# M452sx.net
KiCad netlist of a schematic drawn in EAGLE
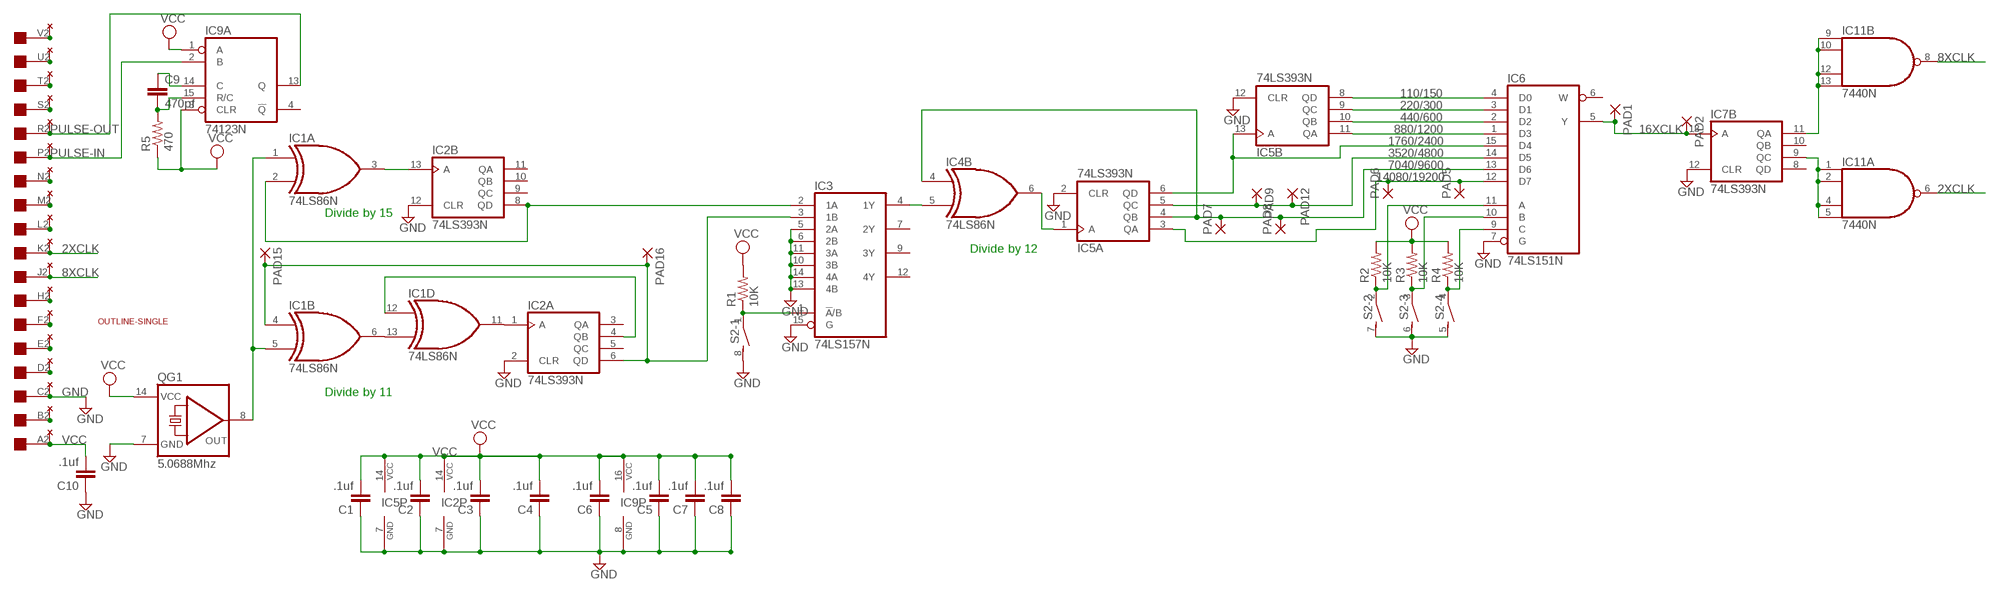
[diagram p0: schematic, sheet 1]

(export (version "E")
  (design (tool "Eeschema 10.0.6"))
  (components
    (comp (ref "C1")
      (value ".1uf")
      (footprint "eagle-import:C050-025X075")
      (libsource (lib "eagle-import") (part "C-EU050-025X075"))
    )
    (comp (ref "C2")
      (value ".1uf")
      (footprint "eagle-import:C050-025X075")
      (libsource (lib "eagle-import") (part "C-EU050-025X075"))
    )
    (comp (ref "C3")
      (value ".1uf")
      (footprint "eagle-import:C050-025X075")
      (libsource (lib "eagle-import") (part "C-EU050-025X075"))
    )
    (comp (ref "C4")
      (value ".1uf")
      (footprint "eagle-import:C050-025X075")
      (libsource (lib "eagle-import") (part "C-EU050-025X075"))
    )
    (comp (ref "C5")
      (value ".1uf")
      (footprint "eagle-import:C050-025X075")
      (libsource (lib "eagle-import") (part "C-EU050-025X075"))
    )
    (comp (ref "C6")
      (value ".1uf")
      (footprint "eagle-import:C050-025X075")
      (libsource (lib "eagle-import") (part "C-EU050-025X075"))
    )
    (comp (ref "C7")
      (value ".1uf")
      (footprint "eagle-import:C050-025X075")
      (libsource (lib "eagle-import") (part "C-EU050-025X075"))
    )
    (comp (ref "C8")
      (value ".1uf")
      (footprint "eagle-import:C050-025X075")
      (libsource (lib "eagle-import") (part "C-EU050-025X075"))
    )
    (comp (ref "C9")
      (value "470pf")
      (footprint "eagle-import:C050-025X075")
      (libsource (lib "eagle-import") (part "C-EU050-025X075"))
    )
    (comp (ref "C10")
      (value ".1uf")
      (footprint "eagle-import:C050-025X075")
      (libsource (lib "eagle-import") (part "C-EU050-025X075"))
    )
    (comp (ref "IC1")
      (value "74LS86N")
      (footprint "eagle-import:DIL14")
      (libsource (lib "eagle-import") (part "7486NLS"))
    )
    (comp (ref "IC2")
      (value "74LS393N")
      (footprint "eagle-import:DIL14")
      (libsource (lib "eagle-import") (part "74393NLS"))
    )
    (comp (ref "IC3")
      (value "74LS157N")
      (footprint "eagle-import:DIL16")
      (libsource (lib "eagle-import") (part "74157NLS"))
    )
    (comp (ref "IC4")
      (value "74LS86N")
      (footprint "eagle-import:DIL14")
      (libsource (lib "eagle-import") (part "7486NLS"))
    )
    (comp (ref "IC5")
      (value "74LS393N")
      (footprint "eagle-import:DIL14")
      (libsource (lib "eagle-import") (part "74393NLS"))
    )
    (comp (ref "IC6")
      (value "74LS151N")
      (footprint "eagle-import:DIL16")
      (libsource (lib "eagle-import") (part "74151N"))
    )
    (comp (ref "IC7")
      (value "74LS393N")
      (footprint "eagle-import:DIL14")
      (libsource (lib "eagle-import") (part "74393NLS"))
    )
    (comp (ref "IC9")
      (value "74123N")
      (footprint "eagle-import:DIL16")
      (libsource (lib "eagle-import") (part "74123N"))
    )
    (comp (ref "IC11")
      (value "7440N")
      (footprint "eagle-import:DIL14")
      (libsource (lib "eagle-import") (part "7420NS"))
    )
    (comp (ref "PAD1")
      (value "1,6/0,8")
      (footprint "eagle-import:1,6_0,8")
      (libsource (lib "eagle-import") (part "1,6/0,8"))
    )
    (comp (ref "PAD2")
      (value "1,6/0,8")
      (footprint "eagle-import:1,6_0,8")
      (libsource (lib "eagle-import") (part "1,6/0,8"))
    )
    (comp (ref "PAD5")
      (value "1,6/0,8")
      (footprint "eagle-import:1,6_0,8")
      (libsource (lib "eagle-import") (part "1,6/0,8"))
    )
    (comp (ref "PAD6")
      (value "1,6/0,8")
      (footprint "eagle-import:1,6_0,8")
      (libsource (lib "eagle-import") (part "1,6/0,8"))
    )
    (comp (ref "PAD7")
      (value "1,6/0,8")
      (footprint "eagle-import:1,6_0,8")
      (libsource (lib "eagle-import") (part "1,6/0,8"))
    )
    (comp (ref "PAD8")
      (value "1,6/0,8")
      (footprint "eagle-import:1,6_0,8")
      (libsource (lib "eagle-import") (part "1,6/0,8"))
    )
    (comp (ref "PAD9")
      (value "1,6/0,8")
      (footprint "eagle-import:1,6_0,8")
      (libsource (lib "eagle-import") (part "1,6/0,8"))
    )
    (comp (ref "PAD12")
      (value "1,6/0,8")
      (footprint "eagle-import:1,6_0,8")
      (libsource (lib "eagle-import") (part "1,6/0,8"))
    )
    (comp (ref "PAD15")
      (value "1,6/0,8")
      (footprint "eagle-import:1,6_0,8")
      (libsource (lib "eagle-import") (part "1,6/0,8"))
    )
    (comp (ref "PAD16")
      (value "1,6/0,8")
      (footprint "eagle-import:1,6_0,8")
      (libsource (lib "eagle-import") (part "1,6/0,8"))
    )
    (comp (ref "QG1")
      (value "5.0688Mhz")
      (footprint "eagle-import:DIL14S")
      (libsource (lib "eagle-import") (part "QG5860"))
    )
    (comp (ref "R1")
      (value "10K")
      (footprint "eagle-import:0204_7")
      (libsource (lib "eagle-import") (part "R-US_0204/7"))
    )
    (comp (ref "R2")
      (value "10K")
      (footprint "eagle-import:0204_7")
      (libsource (lib "eagle-import") (part "R-US_0204/7"))
    )
    (comp (ref "R3")
      (value "10K")
      (footprint "eagle-import:0204_7")
      (libsource (lib "eagle-import") (part "R-US_0204/7"))
    )
    (comp (ref "R4")
      (value "10K")
      (footprint "eagle-import:0204_7")
      (libsource (lib "eagle-import") (part "R-US_0204/7"))
    )
    (comp (ref "R5")
      (value "470")
      (footprint "eagle-import:0204_7")
      (libsource (lib "eagle-import") (part "R-US_0204/7"))
    )
    (comp (ref "S2")
      (value "DIP04S")
      (footprint "eagle-import:DIP04S")
      (libsource (lib "eagle-import") (part "DIP04S"))
    )
    (comp (ref "U$2")
      (value "EDGE-1")
      (footprint "eagle-import:EDGE-CON1")
      (libsource (lib "eagle-import") (part "EDGE-1"))
    )
    (comp (ref "U$3")
      (value "THRU-HOLE1")
      (footprint "eagle-import:THRU-HOLE1")
      (libsource (lib "eagle-import") (part "THRU-HOLE1"))
    )
    (comp (ref "U$4")
      (value "OUTLINE-SINGLE")
      (footprint "eagle-import:SINGLE")
      (libsource (lib "eagle-import") (part "OUTLINE-SINGLE"))
    )
  )
  (nets
    (net (code "1") (name "/2XCLK") (class "Default")
      (node (ref "IC11") (pin "6") (pinfunction "O_6") (pintype "output"))
      (node (ref "U$2") (pin "K2") (pinfunction "1_K2") (pintype "bidirectional"))
      (node (ref "U$3") (pin "K2") (pinfunction "P$1_K2") (pintype "passive"))
    )
    (net (code "2") (name "/8XCLK") (class "Default")
      (node (ref "IC11") (pin "8") (pinfunction "O_8") (pintype "output"))
      (node (ref "U$2") (pin "J2") (pinfunction "1_J2") (pintype "bidirectional"))
      (node (ref "U$3") (pin "J2") (pinfunction "P$1_J2") (pintype "passive"))
    )
    (net (code "3") (name "/16XCLK") (class "Default")
      (node (ref "IC6") (pin "5") (pinfunction "Y_5") (pintype "output"))
      (node (ref "IC7") (pin "13") (pinfunction "A_13") (pintype "input"))
      (node (ref "PAD1") (pin "1") (pinfunction "P_1") (pintype "passive"))
      (node (ref "PAD2") (pin "1") (pinfunction "P_1") (pintype "passive"))
    )
    (net (code "4") (name "/110{slash}150") (class "Default")
      (node (ref "IC5") (pin "8") (pinfunction "QD_8") (pintype "output"))
      (node (ref "IC6") (pin "4") (pinfunction "D0_4") (pintype "input"))
    )
    (net (code "5") (name "/220{slash}300") (class "Default")
      (node (ref "IC5") (pin "9") (pinfunction "QC_9") (pintype "output"))
      (node (ref "IC6") (pin "3") (pinfunction "D1_3") (pintype "input"))
    )
    (net (code "6") (name "/440{slash}600") (class "Default")
      (node (ref "IC5") (pin "10") (pinfunction "QB_10") (pintype "output"))
      (node (ref "IC6") (pin "2") (pinfunction "D2_2") (pintype "input"))
    )
    (net (code "7") (name "/880{slash}1200") (class "Default")
      (node (ref "IC5") (pin "11") (pinfunction "QA_11") (pintype "output"))
      (node (ref "IC6") (pin "1") (pinfunction "D3_1") (pintype "input"))
    )
    (net (code "8") (name "/1760{slash}2400") (class "Default")
      (node (ref "IC5") (pin "13") (pinfunction "A_13") (pintype "input"))
      (node (ref "IC5") (pin "6") (pinfunction "QD_6") (pintype "output"))
      (node (ref "IC6") (pin "15") (pinfunction "D4_15") (pintype "input"))
    )
    (net (code "9") (name "/3520{slash}4800") (class "Default")
      (node (ref "IC5") (pin "5") (pinfunction "QC_5") (pintype "output"))
      (node (ref "IC6") (pin "14") (pinfunction "D5_14") (pintype "input"))
      (node (ref "PAD12") (pin "1") (pinfunction "P_1") (pintype "passive"))
      (node (ref "PAD9") (pin "1") (pinfunction "P_1") (pintype "passive"))
    )
    (net (code "10") (name "/7040{slash}9600") (class "Default")
      (node (ref "IC4") (pin "4") (pinfunction "I0_4") (pintype "input"))
      (node (ref "IC5") (pin "4") (pinfunction "QB_4") (pintype "output"))
      (node (ref "IC6") (pin "13") (pinfunction "D6_13") (pintype "input"))
      (node (ref "PAD7") (pin "1") (pinfunction "P_1") (pintype "passive"))
      (node (ref "PAD8") (pin "1") (pinfunction "P_1") (pintype "passive"))
    )
    (net (code "11") (name "/14080{slash}19200") (class "Default")
      (node (ref "IC5") (pin "3") (pinfunction "QA_3") (pintype "output"))
      (node (ref "IC6") (pin "12") (pinfunction "D7_12") (pintype "input"))
      (node (ref "PAD5") (pin "1") (pinfunction "P_1") (pintype "passive"))
      (node (ref "PAD6") (pin "1") (pinfunction "P_1") (pintype "passive"))
    )
    (net (code "12") (name "/PULSE-IN") (class "Default")
      (node (ref "IC9") (pin "2") (pinfunction "B_2") (pintype "input"))
      (node (ref "U$2") (pin "P2") (pinfunction "1_P2") (pintype "bidirectional"))
      (node (ref "U$3") (pin "P2") (pinfunction "P$1_P2") (pintype "passive"))
    )
    (net (code "13") (name "/PULSE-OUT") (class "Default")
      (node (ref "IC9") (pin "13") (pinfunction "Q_13") (pintype "output"))
      (node (ref "U$2") (pin "R2") (pinfunction "1_R2") (pintype "bidirectional"))
      (node (ref "U$3") (pin "R2") (pinfunction "P$1_R2") (pintype "passive"))
    )
    (net (code "14") (name "GND") (class "Default")
      (node (ref "C1") (pin "1") (pinfunction "1_1") (pintype "passive"))
      (node (ref "C10") (pin "1") (pinfunction "1_1") (pintype "passive"))
      (node (ref "C2") (pin "1") (pinfunction "1_1") (pintype "passive"))
      (node (ref "C3") (pin "1") (pinfunction "1_1") (pintype "passive"))
      (node (ref "C4") (pin "1") (pinfunction "1_1") (pintype "passive"))
      (node (ref "C5") (pin "1") (pinfunction "1_1") (pintype "passive"))
      (node (ref "C6") (pin "1") (pinfunction "1_1") (pintype "passive"))
      (node (ref "C7") (pin "1") (pinfunction "1_1") (pintype "passive"))
      (node (ref "C8") (pin "1") (pinfunction "1_1") (pintype "passive"))
      (node (ref "IC2") (pin "12") (pinfunction "CLR_12") (pintype "input"))
      (node (ref "IC2") (pin "2") (pinfunction "CLR_2") (pintype "input"))
      (node (ref "IC2") (pin "7") (pinfunction "GND_7") (pintype "power_in"))
      (node (ref "IC3") (pin "10") (pinfunction "3B_10") (pintype "input"))
      (node (ref "IC3") (pin "11") (pinfunction "3A_11") (pintype "input"))
      (node (ref "IC3") (pin "13") (pinfunction "4B_13") (pintype "input"))
      (node (ref "IC3") (pin "14") (pinfunction "4A_14") (pintype "input"))
      (node (ref "IC3") (pin "15") (pinfunction "G_15") (pintype "input"))
      (node (ref "IC3") (pin "5") (pinfunction "2A_5") (pintype "input"))
      (node (ref "IC3") (pin "6") (pinfunction "2B_6") (pintype "input"))
      (node (ref "IC5") (pin "12") (pinfunction "CLR_12") (pintype "input"))
      (node (ref "IC5") (pin "2") (pinfunction "CLR_2") (pintype "input"))
      (node (ref "IC5") (pin "7") (pinfunction "GND_7") (pintype "power_in"))
      (node (ref "IC6") (pin "7") (pinfunction "G_7") (pintype "input"))
      (node (ref "IC7") (pin "12") (pinfunction "CLR_12") (pintype "input"))
      (node (ref "IC9") (pin "8") (pinfunction "GND_8") (pintype "power_in"))
      (node (ref "QG1") (pin "7") (pinfunction "GND_7") (pintype "power_in"))
      (node (ref "S2") (pin "5") (pinfunction "2_5") (pintype "passive"))
      (node (ref "S2") (pin "6") (pinfunction "2_6") (pintype "passive"))
      (node (ref "S2") (pin "7") (pinfunction "2_7") (pintype "passive"))
      (node (ref "S2") (pin "8") (pinfunction "2_8") (pintype "passive"))
      (node (ref "U$2") (pin "C2") (pinfunction "1_C2") (pintype "bidirectional"))
      (node (ref "U$3") (pin "C2") (pinfunction "P$1_C2") (pintype "passive"))
    )
    (net (code "15") (name "Net-(IC1A-I0)") (class "Default")
      (node (ref "IC1") (pin "1") (pinfunction "I0_1") (pintype "input"))
      (node (ref "IC1") (pin "5") (pinfunction "I1_5") (pintype "input"))
      (node (ref "QG1") (pin "8") (pinfunction "OUT_8") (pintype "output"))
    )
    (net (code "16") (name "Net-(IC1A-I1)") (class "Default")
      (node (ref "IC1") (pin "2") (pinfunction "I1_2") (pintype "input"))
      (node (ref "IC2") (pin "8") (pinfunction "QD_8") (pintype "output"))
      (node (ref "IC3") (pin "2") (pinfunction "1A_2") (pintype "input"))
    )
    (net (code "17") (name "Net-(IC1A-O)") (class "Default")
      (node (ref "IC1") (pin "3") (pinfunction "O_3") (pintype "output"))
      (node (ref "IC2") (pin "13") (pinfunction "A_13") (pintype "input"))
    )
    (net (code "18") (name "Net-(IC1B-I0)") (class "Default")
      (node (ref "IC1") (pin "4") (pinfunction "I0_4") (pintype "input"))
      (node (ref "IC2") (pin "6") (pinfunction "QD_6") (pintype "output"))
      (node (ref "IC3") (pin "3") (pinfunction "1B_3") (pintype "input"))
      (node (ref "PAD15") (pin "1") (pinfunction "P_1") (pintype "passive"))
      (node (ref "PAD16") (pin "1") (pinfunction "P_1") (pintype "passive"))
    )
    (net (code "19") (name "Net-(IC1B-O)") (class "Default")
      (node (ref "IC1") (pin "13") (pinfunction "I1_13") (pintype "input"))
      (node (ref "IC1") (pin "6") (pinfunction "O_6") (pintype "output"))
    )
    (net (code "20") (name "Net-(IC1D-I0)") (class "Default")
      (node (ref "IC1") (pin "12") (pinfunction "I0_12") (pintype "input"))
      (node (ref "IC2") (pin "4") (pinfunction "QB_4") (pintype "output"))
    )
    (net (code "21") (name "Net-(IC1D-O)") (class "Default")
      (node (ref "IC1") (pin "11") (pinfunction "O_11") (pintype "output"))
      (node (ref "IC2") (pin "1") (pinfunction "A_1") (pintype "input"))
    )
    (net (code "22") (name "Net-(IC3A-1Y)") (class "Default")
      (node (ref "IC3") (pin "4") (pinfunction "1Y_4") (pintype "output"))
      (node (ref "IC4") (pin "5") (pinfunction "I1_5") (pintype "input"))
    )
    (net (code "23") (name "Net-(IC3A-~{A}{slash}B)") (class "Default")
      (node (ref "IC3") (pin "1") (pinfunction "~{A}/B_1") (pintype "input"))
      (node (ref "R1") (pin "1") (pinfunction "1_1") (pintype "passive"))
      (node (ref "S2") (pin "1") (pinfunction "1_1") (pintype "passive"))
    )
    (net (code "24") (name "Net-(IC4B-O)") (class "Default")
      (node (ref "IC4") (pin "6") (pinfunction "O_6") (pintype "output"))
      (node (ref "IC5") (pin "1") (pinfunction "A_1") (pintype "input"))
    )
    (net (code "25") (name "Net-(IC6A-A)") (class "Default")
      (node (ref "IC6") (pin "11") (pinfunction "A_11") (pintype "input"))
      (node (ref "R2") (pin "1") (pinfunction "1_1") (pintype "passive"))
      (node (ref "S2") (pin "2") (pinfunction "1_2") (pintype "passive"))
    )
    (net (code "26") (name "Net-(IC6A-B)") (class "Default")
      (node (ref "IC6") (pin "10") (pinfunction "B_10") (pintype "input"))
      (node (ref "R3") (pin "1") (pinfunction "1_1") (pintype "passive"))
      (node (ref "S2") (pin "3") (pinfunction "1_3") (pintype "passive"))
    )
    (net (code "27") (name "Net-(IC6A-C)") (class "Default")
      (node (ref "IC6") (pin "9") (pinfunction "C_9") (pintype "input"))
      (node (ref "R4") (pin "1") (pinfunction "1_1") (pintype "passive"))
      (node (ref "S2") (pin "4") (pinfunction "1_4") (pintype "passive"))
    )
    (net (code "28") (name "Net-(IC9A-C)") (class "Default")
      (node (ref "C9") (pin "1") (pinfunction "1_1") (pintype "passive"))
      (node (ref "IC9") (pin "14") (pinfunction "C_14") (pintype "input"))
    )
    (net (code "29") (name "Net-(IC9A-R{slash}C)") (class "Default")
      (node (ref "C9") (pin "2") (pinfunction "2_2") (pintype "passive"))
      (node (ref "IC9") (pin "15") (pinfunction "R/C_15") (pintype "input"))
      (node (ref "R5") (pin "2") (pinfunction "2_2") (pintype "passive"))
    )
    (net (code "30") (name "Net-(IC11A-I0)") (class "Default")
      (node (ref "IC11") (pin "1") (pinfunction "I0_1") (pintype "input"))
      (node (ref "IC11") (pin "2") (pinfunction "I1_2") (pintype "input"))
      (node (ref "IC11") (pin "4") (pinfunction "I2_4") (pintype "input"))
      (node (ref "IC11") (pin "5") (pinfunction "I3_5") (pintype "input"))
      (node (ref "IC7") (pin "9") (pinfunction "QC_9") (pintype "output"))
    )
    (net (code "31") (name "Net-(IC11B-I0)") (class "Default")
      (node (ref "IC11") (pin "10") (pinfunction "I1_10") (pintype "input"))
      (node (ref "IC11") (pin "12") (pinfunction "I2_12") (pintype "input"))
      (node (ref "IC11") (pin "13") (pinfunction "I3_13") (pintype "input"))
      (node (ref "IC11") (pin "9") (pinfunction "I0_9") (pintype "input"))
      (node (ref "IC7") (pin "11") (pinfunction "QA_11") (pintype "output"))
    )
    (net (code "32") (name "Net-(U$2B-1)") (class "Default")
      (node (ref "U$2") (pin "B2") (pinfunction "1_B2") (pintype "bidirectional"))
      (node (ref "U$3") (pin "B2") (pinfunction "P$1_B2") (pintype "passive"))
    )
    (net (code "33") (name "Net-(U$2D-1)") (class "Default")
      (node (ref "U$2") (pin "D2") (pinfunction "1_D2") (pintype "bidirectional"))
      (node (ref "U$3") (pin "D2") (pinfunction "P$1_D2") (pintype "passive"))
    )
    (net (code "34") (name "Net-(U$2E-1)") (class "Default")
      (node (ref "U$2") (pin "E2") (pinfunction "1_E2") (pintype "bidirectional"))
      (node (ref "U$3") (pin "E2") (pinfunction "P$1_E2") (pintype "passive"))
    )
    (net (code "35") (name "Net-(U$2F-1)") (class "Default")
      (node (ref "U$2") (pin "F2") (pinfunction "1_F2") (pintype "bidirectional"))
      (node (ref "U$3") (pin "F2") (pinfunction "P$1_F2") (pintype "passive"))
    )
    (net (code "36") (name "Net-(U$2G-1)") (class "Default")
      (node (ref "U$2") (pin "H2") (pinfunction "1_H2") (pintype "bidirectional"))
      (node (ref "U$3") (pin "H2") (pinfunction "P$1_H2") (pintype "passive"))
    )
    (net (code "37") (name "Net-(U$2J-1)") (class "Default")
      (node (ref "U$2") (pin "L2") (pinfunction "1_L2") (pintype "bidirectional"))
      (node (ref "U$3") (pin "L2") (pinfunction "P$1_L2") (pintype "passive"))
    )
    (net (code "38") (name "Net-(U$2K-1)") (class "Default")
      (node (ref "U$2") (pin "M2") (pinfunction "1_M2") (pintype "bidirectional"))
      (node (ref "U$3") (pin "M2") (pinfunction "P$1_M2") (pintype "passive"))
    )
    (net (code "39") (name "Net-(U$2L-1)") (class "Default")
      (node (ref "U$2") (pin "N2") (pinfunction "1_N2") (pintype "bidirectional"))
      (node (ref "U$3") (pin "N2") (pinfunction "P$1_N2") (pintype "passive"))
    )
    (net (code "40") (name "Net-(U$2O-1)") (class "Default")
      (node (ref "U$2") (pin "S2") (pinfunction "1_S2") (pintype "bidirectional"))
      (node (ref "U$3") (pin "S2") (pinfunction "P$1_S2") (pintype "passive"))
    )
    (net (code "41") (name "Net-(U$2P-1)") (class "Default")
      (node (ref "U$2") (pin "T2") (pinfunction "1_T2") (pintype "bidirectional"))
      (node (ref "U$3") (pin "T2") (pinfunction "P$1_T2") (pintype "passive"))
    )
    (net (code "42") (name "Net-(U$2Q-1)") (class "Default")
      (node (ref "U$2") (pin "U2") (pinfunction "1_U2") (pintype "bidirectional"))
      (node (ref "U$3") (pin "U2") (pinfunction "P$1_U2") (pintype "passive"))
    )
    (net (code "43") (name "Net-(U$2R-1)") (class "Default")
      (node (ref "U$2") (pin "V2") (pinfunction "1_V2") (pintype "bidirectional"))
      (node (ref "U$3") (pin "V2") (pinfunction "P$1_V2") (pintype "passive"))
    )
    (net (code "44") (name "VCC") (class "Default")
      (node (ref "C1") (pin "2") (pinfunction "2_2") (pintype "passive"))
      (node (ref "C10") (pin "2") (pinfunction "2_2") (pintype "passive"))
      (node (ref "C2") (pin "2") (pinfunction "2_2") (pintype "passive"))
      (node (ref "C3") (pin "2") (pinfunction "2_2") (pintype "passive"))
      (node (ref "C4") (pin "2") (pinfunction "2_2") (pintype "passive"))
      (node (ref "C5") (pin "2") (pinfunction "2_2") (pintype "passive"))
      (node (ref "C6") (pin "2") (pinfunction "2_2") (pintype "passive"))
      (node (ref "C7") (pin "2") (pinfunction "2_2") (pintype "passive"))
      (node (ref "C8") (pin "2") (pinfunction "2_2") (pintype "passive"))
      (node (ref "IC2") (pin "14") (pinfunction "VCC_14") (pintype "power_in"))
      (node (ref "IC5") (pin "14") (pinfunction "VCC_14") (pintype "power_in"))
      (node (ref "IC9") (pin "1") (pinfunction "A_1") (pintype "input"))
      (node (ref "IC9") (pin "16") (pinfunction "VCC_16") (pintype "power_in"))
      (node (ref "IC9") (pin "3") (pinfunction "CLR_3") (pintype "input"))
      (node (ref "QG1") (pin "14") (pinfunction "VCC_14") (pintype "power_in"))
      (node (ref "R1") (pin "2") (pinfunction "2_2") (pintype "passive"))
      (node (ref "R2") (pin "2") (pinfunction "2_2") (pintype "passive"))
      (node (ref "R3") (pin "2") (pinfunction "2_2") (pintype "passive"))
      (node (ref "R4") (pin "2") (pinfunction "2_2") (pintype "passive"))
      (node (ref "R5") (pin "1") (pinfunction "1_1") (pintype "passive"))
      (node (ref "U$2") (pin "A2") (pinfunction "1_A2") (pintype "bidirectional"))
      (node (ref "U$3") (pin "A2") (pinfunction "P$1_A2") (pintype "passive"))
    )
    (net (code "45") (name "unconnected-(IC2A-QA-Pad3)") (class "Default")
      (node (ref "IC2") (pin "3") (pinfunction "QA_3") (pintype "output"))
    )
    (net (code "46") (name "unconnected-(IC2A-QC-Pad5)") (class "Default")
      (node (ref "IC2") (pin "5") (pinfunction "QC_5") (pintype "output"))
    )
    (net (code "47") (name "unconnected-(IC2B-QA-Pad11)") (class "Default")
      (node (ref "IC2") (pin "11") (pinfunction "QA_11") (pintype "output"))
    )
    (net (code "48") (name "unconnected-(IC2B-QB-Pad10)") (class "Default")
      (node (ref "IC2") (pin "10") (pinfunction "QB_10") (pintype "output"))
    )
    (net (code "49") (name "unconnected-(IC2B-QC-Pad9)") (class "Default")
      (node (ref "IC2") (pin "9") (pinfunction "QC_9") (pintype "output"))
    )
    (net (code "50") (name "unconnected-(IC3A-2Y-Pad7)") (class "Default")
      (node (ref "IC3") (pin "7") (pinfunction "2Y_7") (pintype "output"))
    )
    (net (code "51") (name "unconnected-(IC3A-3Y-Pad9)") (class "Default")
      (node (ref "IC3") (pin "9") (pinfunction "3Y_9") (pintype "output"))
    )
    (net (code "52") (name "unconnected-(IC3A-4Y-Pad12)") (class "Default")
      (node (ref "IC3") (pin "12") (pinfunction "4Y_12") (pintype "output"))
    )
    (net (code "53") (name "unconnected-(IC6A-W-Pad6)") (class "Default")
      (node (ref "IC6") (pin "6") (pinfunction "W_6") (pintype "output"))
    )
    (net (code "54") (name "unconnected-(IC7B-QB-Pad10)") (class "Default")
      (node (ref "IC7") (pin "10") (pinfunction "QB_10") (pintype "output"))
    )
    (net (code "55") (name "unconnected-(IC7B-QD-Pad8)") (class "Default")
      (node (ref "IC7") (pin "8") (pinfunction "QD_8") (pintype "output"))
    )
    (net (code "56") (name "unconnected-(IC9A-~{Q}-Pad4)") (class "Default")
      (node (ref "IC9") (pin "4") (pinfunction "~{Q}_4") (pintype "output"))
    )
  )
)
